# 03_Sensors_and_WirelessCommunication.net
KiCad netlist of a schematic drawn in Altium Designer
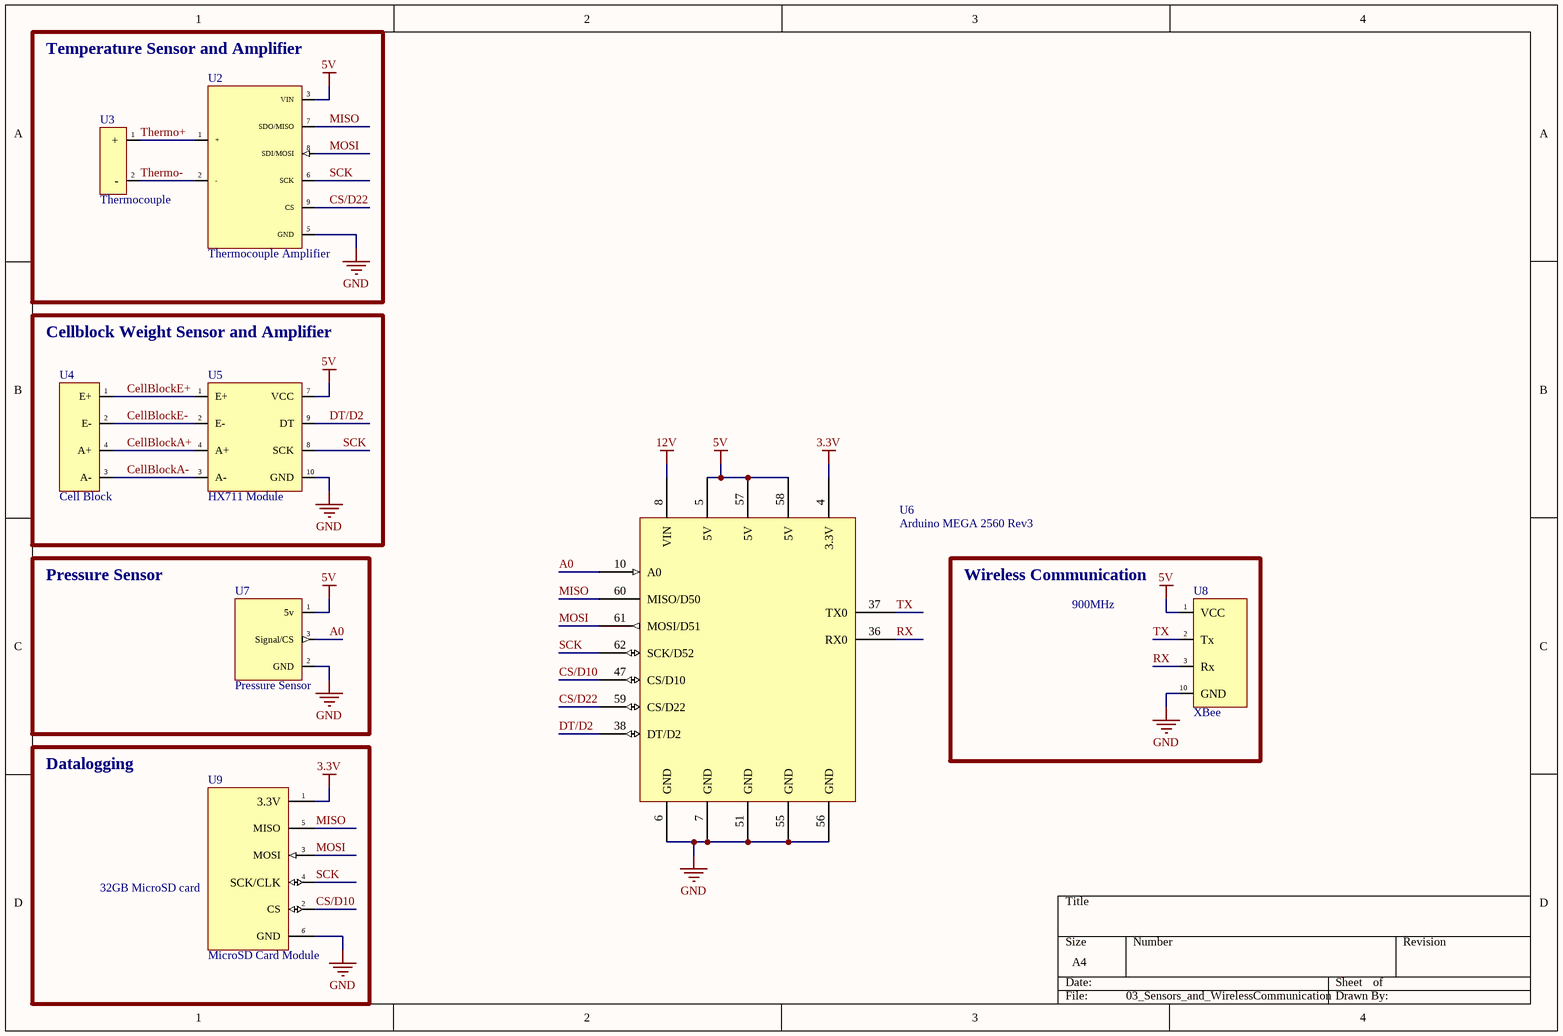
[diagram p0: 03_Sensors_and_WirelessCommunication.SchDoc]

(export (version "E")
  (design (tool "Eeschema 10.0.6"))
  (components
    (comp (ref "U2")
      (value "Thermocouple Amplifier")
      (footprint "Thermocouple Amplifier")
      (libsource (lib "Ground Support_Schlib") (part "Thermocouple Amplifier"))
    )
    (comp (ref "U3")
      (value "Thermocouple")
      (footprint "Thermocouple")
      (libsource (lib "Ground Support_Schlib") (part "Thermocouple"))
    )
    (comp (ref "U4")
      (value "Cell Block")
      (footprint "Cell Block")
      (libsource (lib "Ground Support_Schlib") (part "Cell Block"))
    )
    (comp (ref "U5")
      (value "HX711 Module")
      (footprint "HX711 Module")
      (libsource (lib "Ground Support_Schlib") (part "HX711 Module"))
    )
    (comp (ref "U6")
      (value "Arduino MEGA 2560 Rev3")
      (footprint "Arduino MEGA 2560")
      (libsource (lib "Ground Support_Schlib") (part "Arduino MEGA 2560"))
    )
    (comp (ref "U7")
      (value "Pressure Sensor")
      (footprint "Pressure Sensor")
      (libsource (lib "Ground Support_Schlib") (part "Pressure Sensor"))
    )
    (comp (ref "U8")
      (value "XBee")
      (footprint "XBee")
      (libsource (lib "Ground Support_Schlib") (part "XBee"))
    )
    (comp (ref "U9")
      (value "MicroSD Card Module")
      (footprint "MicroSD Card Module")
      (libsource (lib "Ground Support_Schlib") (part "MicroSD Card Module"))
    )
  )
  (nets
    (net (code "1") (name "/A0") (class "Default")
      (node (ref "U6") (pin "10") (pinfunction "A0_10") (pintype "input"))
      (node (ref "U7") (pin "3") (pinfunction "Signal/CS_3") (pintype "output"))
    )
    (net (code "2") (name "/CS{slash}D10") (class "Default")
      (node (ref "U6") (pin "47") (pinfunction "CS/D10_47") (pintype "bidirectional"))
      (node (ref "U9") (pin "2") (pinfunction "CS_2") (pintype "bidirectional"))
    )
    (net (code "3") (name "/CS{slash}D22") (class "Default")
      (node (ref "U2") (pin "9") (pinfunction "CS_9") (pintype "bidirectional"))
      (node (ref "U6") (pin "59") (pinfunction "CS/D22_59") (pintype "bidirectional"))
    )
    (net (code "4") (name "/CellBlockA+") (class "Default")
      (node (ref "U4") (pin "4") (pinfunction "A+_4") (pintype "passive"))
      (node (ref "U5") (pin "4") (pinfunction "A+_4") (pintype "passive"))
    )
    (net (code "5") (name "/CellBlockA-") (class "Default")
      (node (ref "U4") (pin "3") (pinfunction "A-_3") (pintype "passive"))
      (node (ref "U5") (pin "3") (pinfunction "A-_3") (pintype "passive"))
    )
    (net (code "6") (name "/CellBlockE+") (class "Default")
      (node (ref "U4") (pin "1") (pinfunction "E+_1") (pintype "passive"))
      (node (ref "U5") (pin "1") (pinfunction "E+_1") (pintype "passive"))
    )
    (net (code "7") (name "/CellBlockE-") (class "Default")
      (node (ref "U4") (pin "2") (pinfunction "E-_2") (pintype "passive"))
      (node (ref "U5") (pin "2") (pinfunction "E-_2") (pintype "passive"))
    )
    (net (code "8") (name "/DT{slash}D2") (class "Default")
      (node (ref "U5") (pin "9") (pinfunction "DT_9") (pintype "bidirectional"))
      (node (ref "U6") (pin "38") (pinfunction "DT/D2_38") (pintype "bidirectional"))
    )
    (net (code "9") (name "/MISO") (class "Default")
      (node (ref "U2") (pin "7") (pinfunction "SDO/MISO_7") (pintype "passive"))
      (node (ref "U6") (pin "60") (pinfunction "MISO/D50_60") (pintype "passive"))
      (node (ref "U9") (pin "5") (pinfunction "MISO_5") (pintype "passive"))
    )
    (net (code "10") (name "/MOSI") (class "Default")
      (node (ref "U2") (pin "8") (pinfunction "SDI/MOSI_8") (pintype "input"))
      (node (ref "U6") (pin "61") (pinfunction "MOSI/D51_61") (pintype "output"))
      (node (ref "U9") (pin "3") (pinfunction "MOSI_3") (pintype "input"))
    )
    (net (code "11") (name "/RX") (class "Default")
      (node (ref "U6") (pin "36") (pinfunction "RX0_36") (pintype "passive"))
      (node (ref "U8") (pin "3") (pinfunction "Rx_3") (pintype "passive"))
    )
    (net (code "12") (name "/SCK") (class "Default")
      (node (ref "U2") (pin "6") (pinfunction "SCK_6") (pintype "bidirectional"))
      (node (ref "U5") (pin "8") (pinfunction "SCK_8") (pintype "bidirectional"))
      (node (ref "U6") (pin "62") (pinfunction "SCK/D52_62") (pintype "bidirectional"))
      (node (ref "U9") (pin "4") (pinfunction "SCK/CLK_4") (pintype "bidirectional"))
    )
    (net (code "13") (name "/TX") (class "Default")
      (node (ref "U6") (pin "37") (pinfunction "TX0_37") (pintype "passive"))
      (node (ref "U8") (pin "2") (pinfunction "Tx_2") (pintype "passive"))
    )
    (net (code "14") (name "/Thermo+") (class "Default")
      (node (ref "U2") (pin "1") (pinfunction "+_1") (pintype "power_in"))
      (node (ref "U3") (pin "1") (pinfunction "+_1") (pintype "power_in"))
    )
    (net (code "15") (name "/Thermo-") (class "Default")
      (node (ref "U2") (pin "2") (pinfunction "-_2") (pintype "power_in"))
      (node (ref "U3") (pin "2") (pinfunction "-_2") (pintype "power_in"))
    )
    (net (code "16") (name "3.3V") (class "Default")
      (node (ref "U6") (pin "4") (pinfunction "3.3V_4") (pintype "power_in"))
      (node (ref "U9") (pin "1") (pinfunction "3.3V_1") (pintype "power_in"))
    )
    (net (code "17") (name "5V") (class "Default")
      (node (ref "U2") (pin "3") (pinfunction "VIN_3") (pintype "power_in"))
      (node (ref "U5") (pin "7") (pinfunction "VCC_7") (pintype "power_in"))
      (node (ref "U6") (pin "5") (pinfunction "5V_5") (pintype "power_in"))
      (node (ref "U6") (pin "57") (pinfunction "5V_57") (pintype "power_in"))
      (node (ref "U6") (pin "58") (pinfunction "5V_58") (pintype "power_in"))
      (node (ref "U7") (pin "1") (pinfunction "5v_1") (pintype "power_in"))
      (node (ref "U8") (pin "1") (pinfunction "VCC_1") (pintype "power_in"))
    )
    (net (code "18") (name "12V") (class "Default")
      (node (ref "U6") (pin "8") (pinfunction "VIN_8") (pintype "power_in"))
    )
    (net (code "19") (name "GND") (class "Default")
      (node (ref "U2") (pin "5") (pinfunction "GND_5") (pintype "power_in"))
      (node (ref "U5") (pin "10") (pinfunction "GND_10") (pintype "power_in"))
      (node (ref "U6") (pin "51") (pinfunction "GND_51") (pintype "power_in"))
      (node (ref "U6") (pin "55") (pinfunction "GND_55") (pintype "power_in"))
      (node (ref "U6") (pin "56") (pinfunction "GND_56") (pintype "power_in"))
      (node (ref "U6") (pin "6") (pinfunction "GND_6") (pintype "power_in"))
      (node (ref "U6") (pin "7") (pinfunction "GND_7") (pintype "power_in"))
      (node (ref "U7") (pin "2") (pinfunction "GND_2") (pintype "power_in"))
      (node (ref "U8") (pin "10") (pinfunction "GND_10") (pintype "power_in"))
      (node (ref "U9") (pin "6") (pinfunction "GND_6") (pintype "power_in"))
    )
  )
)
